# sc14cvm-evb.net
KiCad netlist of a schematic drawn in EAGLE
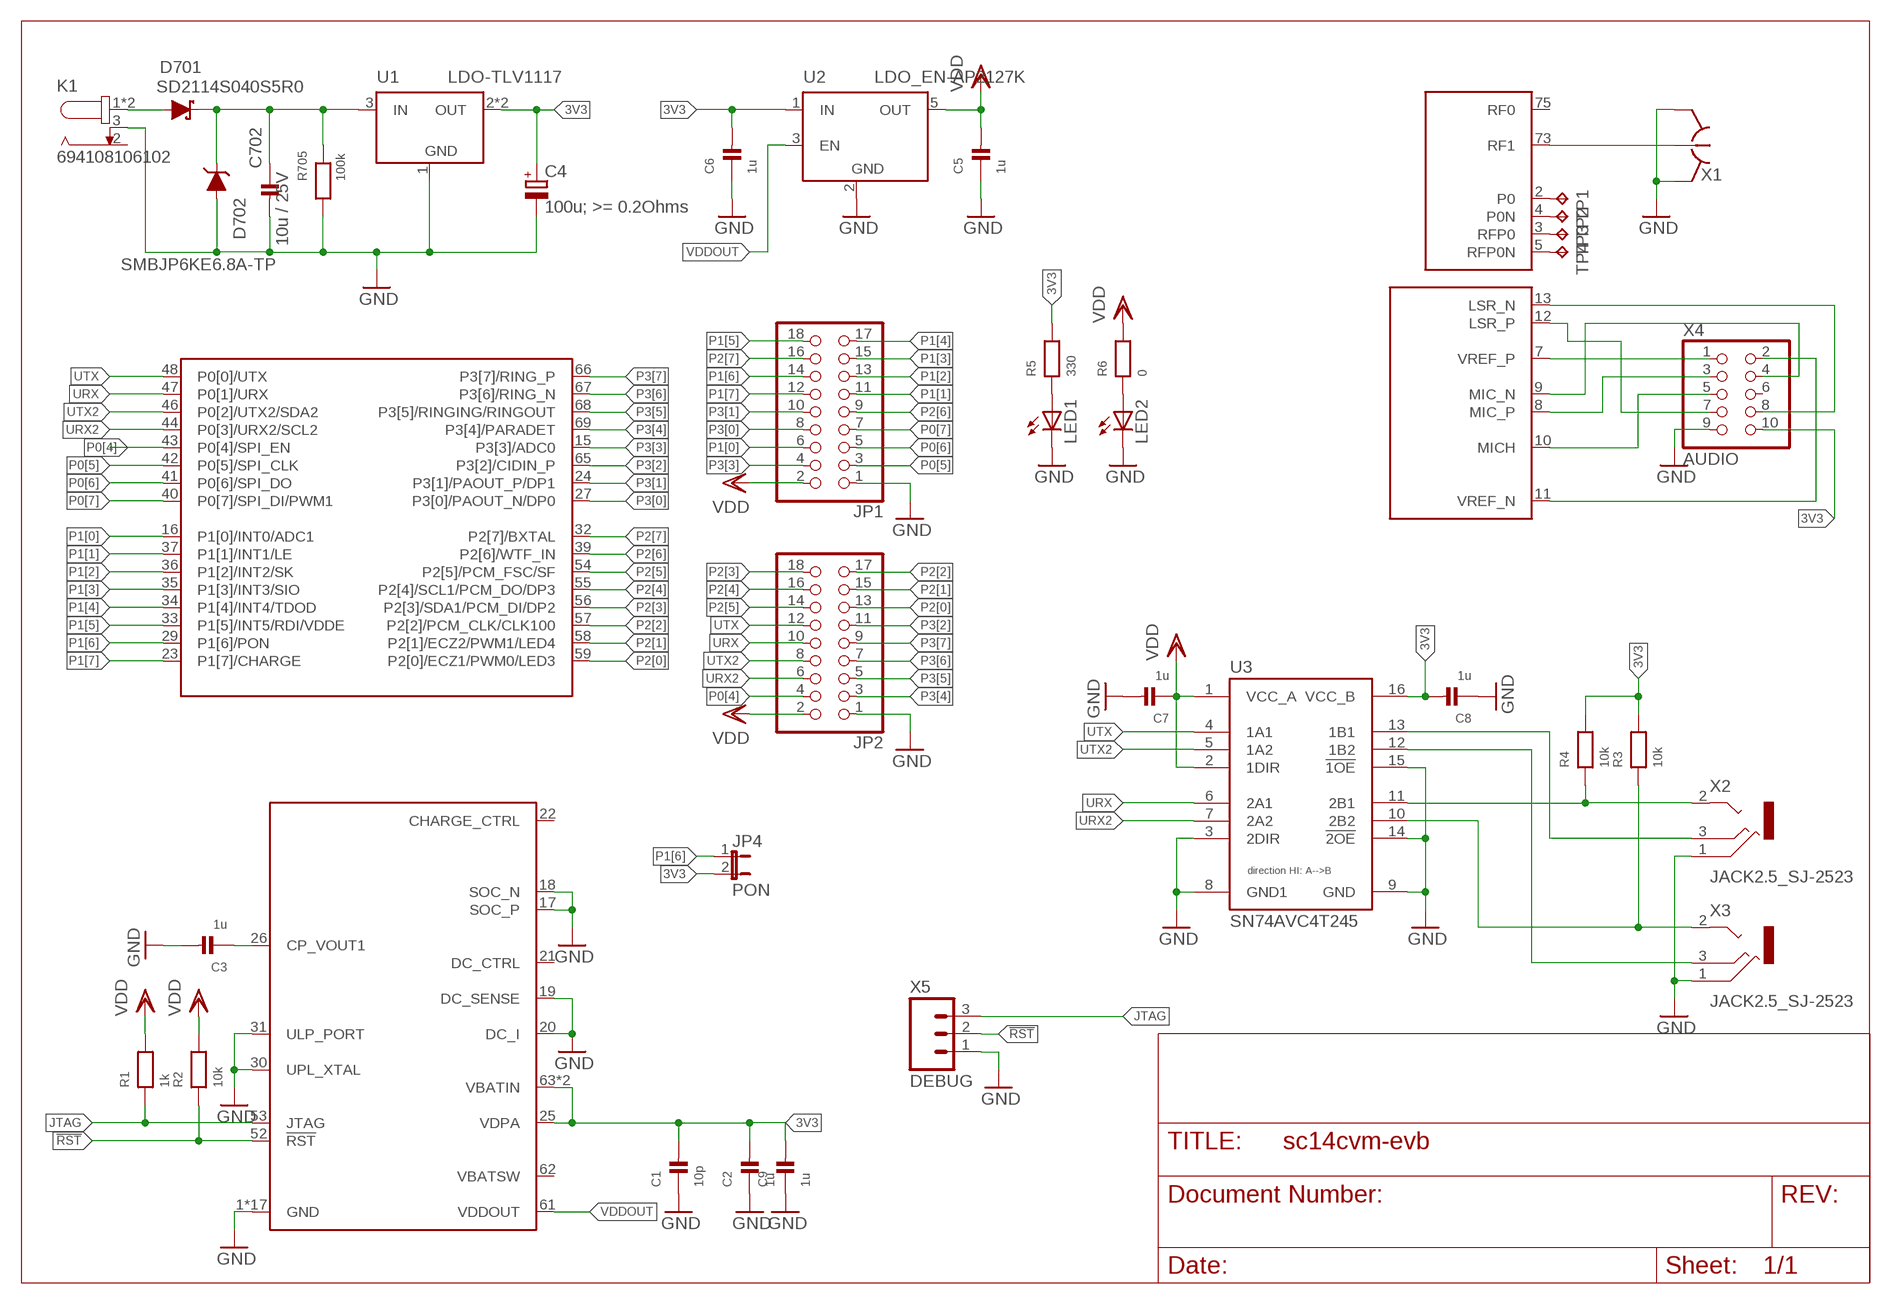
[diagram p0: schematic, sheet 1]

(export (version "E")
  (design (tool "Eeschema 10.0.6"))
  (components
    (comp (ref "C1")
      (value "10p")
      (footprint "eagle-import:_0402")
      (description "NO DESCRIPTION")
      (fields
        (field (name "MANUFACTURER") "UNKNOWN MANUFACTURER")
        (field (name "MANUFACTURERPARTNUMBER") "UNKNOWN MANUFACTURER PART NUMBER")
      )
      (libsource (lib "eagle-import") (part "CAP_CERAMIC_0402"))
    )
    (comp (ref "C2")
      (value "1u")
      (footprint "eagle-import:_0402")
      (description "NO DESCRIPTION")
      (fields
        (field (name "MANUFACTURER") "UNKNOWN MANUFACTURER")
        (field (name "MANUFACTURERPARTNUMBER") "UNKNOWN MANUFACTURER PART NUMBER")
      )
      (libsource (lib "eagle-import") (part "CAP_CERAMIC_0402"))
    )
    (comp (ref "C3")
      (value "1u")
      (footprint "eagle-import:_0603")
      (description "NO DESCRIPTION")
      (fields
        (field (name "MANUFACTURER") "UNKNOWN MANUFACTURER")
        (field (name "MANUFACTURERPARTNUMBER") "UNKNOWN MANUFACTURER PART NUMBER")
      )
      (libsource (lib "eagle-import") (part "CAP_CERAMIC_0603"))
    )
    (comp (ref "C4")
      (value "100u; >= 0.2Ohms")
      (footprint "eagle-import:SMC_B")
      (description "NO DESCRIPTION")
      (fields
        (field (name "MANUFACTURER") "UNKNOWN MANUFACTURER")
        (field (name "MANUFACTURERPARTNUMBER") "UNKNOWN MANUFACTURER PART NUMBER")
      )
      (libsource (lib "eagle-import") (part "CPOL-EUSMCB"))
    )
    (comp (ref "C5")
      (value "1u")
      (footprint "eagle-import:_0603")
      (description "NO DESCRIPTION")
      (fields
        (field (name "MANUFACTURER") "UNKNOWN MANUFACTURER")
        (field (name "MANUFACTURERPARTNUMBER") "UNKNOWN MANUFACTURER PART NUMBER")
      )
      (libsource (lib "eagle-import") (part "CAP_CERAMIC_0603"))
    )
    (comp (ref "C6")
      (value "1u")
      (footprint "eagle-import:_0603")
      (description "NO DESCRIPTION")
      (fields
        (field (name "MANUFACTURER") "UNKNOWN MANUFACTURER")
        (field (name "MANUFACTURERPARTNUMBER") "UNKNOWN MANUFACTURER PART NUMBER")
      )
      (libsource (lib "eagle-import") (part "CAP_CERAMIC_0603"))
    )
    (comp (ref "C7")
      (value "1u")
      (footprint "eagle-import:_0603")
      (description "NO DESCRIPTION")
      (fields
        (field (name "MANUFACTURER") "UNKNOWN MANUFACTURER")
        (field (name "MANUFACTURERPARTNUMBER") "UNKNOWN MANUFACTURER PART NUMBER")
      )
      (libsource (lib "eagle-import") (part "CAP_CERAMIC_0603"))
    )
    (comp (ref "C8")
      (value "1u")
      (footprint "eagle-import:_0603")
      (description "NO DESCRIPTION")
      (fields
        (field (name "MANUFACTURER") "UNKNOWN MANUFACTURER")
        (field (name "MANUFACTURERPARTNUMBER") "UNKNOWN MANUFACTURER PART NUMBER")
      )
      (libsource (lib "eagle-import") (part "CAP_CERAMIC_0603"))
    )
    (comp (ref "C9")
      (value "1u")
      (footprint "eagle-import:_0402")
      (description "NO DESCRIPTION")
      (fields
        (field (name "MANUFACTURER") "UNKNOWN MANUFACTURER")
        (field (name "MANUFACTURERPARTNUMBER") "UNKNOWN MANUFACTURER PART NUMBER")
      )
      (libsource (lib "eagle-import") (part "CAP_CERAMIC_0402"))
    )
    (comp (ref "C702")
      (value "10u / 25V")
      (footprint "eagle-import:C1812K")
      (description "CAP CER 10UF 25V X7R 1812")
      (fields
        (field (name "MANUFACTURER") "TDK Corporation")
        (field (name "MANUFACTURERPARTNUMBER") "C4532X7R1E106M250KA")
      )
      (libsource (lib "eagle-import") (part "CAP_CERAMIC-C1812"))
    )
    (comp (ref "D701")
      (value "SD2114S040S5R0")
      (footprint "eagle-import:SMBDIODE")
      (description "DIODE SCHOTTKY 40V 5A SMB")
      (fields (field (name "MANUFACTURER") "AVX Corporation"))
      (libsource (lib "eagle-import") (part "DIODE-SCHOTTKY-SMB"))
    )
    (comp (ref "D702")
      (value "SMBJP6KE6.8A-TP")
      (footprint "eagle-import:SMBDIODE")
      (description "TVS DIODE 5.8V 10.5V DO214AA")
      (fields (field (name "MANUFACTURER") "Micro Commercial Co"))
      (libsource (lib "eagle-import") (part "DIODE-TVS-SMB"))
    )
    (comp (ref "JP1")
      (value "PINHD-2X9")
      (footprint "eagle-import:2X09")
      (description "NO DESCRIPTION")
      (fields
        (field (name "MANUFACTURER") "UNKNOWN MANUFACTURER")
        (field (name "MANUFACTURERPARTNUMBER") "UNKNOWN MANUFACTURER PART NUMBER")
      )
      (libsource (lib "eagle-import") (part "PINHD-2X9"))
    )
    (comp (ref "JP2")
      (value "PINHD-2X9")
      (footprint "eagle-import:2X09")
      (description "NO DESCRIPTION")
      (fields
        (field (name "MANUFACTURER") "UNKNOWN MANUFACTURER")
        (field (name "MANUFACTURERPARTNUMBER") "UNKNOWN MANUFACTURER PART NUMBER")
      )
      (libsource (lib "eagle-import") (part "PINHD-2X9"))
    )
    (comp (ref "JP4")
      (value "PON")
      (footprint "eagle-import:JP1")
      (description "NO DESCRIPTION")
      (fields
        (field (name "MANUFACTURER") "UNKNOWN MANUFACTURER")
        (field (name "MANUFACTURERPARTNUMBER") "UNKNOWN MANUFACTURER PART NUMBER")
      )
      (libsource (lib "eagle-import") (part "JP1E"))
    )
    (comp (ref "K1")
      (value "694108106102")
      (footprint "eagle-import:694108106102")
      (description "NO DESCRIPTION")
      (fields
        (field (name "MANUFACTURER") "UNKNOWN MANUFACTURER")
        (field (name "MANUFACTURERPARTNUMBER") "UNKNOWN MANUFACTURER PART NUMBER")
      )
      (libsource (lib "eagle-import") (part "694108106102"))
    )
    (comp (ref "LED1")
      (value "LEDCHIPLED_0603")
      (footprint "eagle-import:CHIPLED_0603")
      (description "NO DESCRIPTION")
      (fields
        (field (name "MANUFACTURER") "UNKNOWN MANUFACTURER")
        (field (name "MANUFACTURERPARTNUMBER") "UNKNOWN MANUFACTURER PART NUMBER")
      )
      (libsource (lib "eagle-import") (part "LEDCHIPLED_0603"))
    )
    (comp (ref "LED2")
      (value "LEDCHIPLED_0603")
      (footprint "eagle-import:CHIPLED_0603")
      (description "NO DESCRIPTION")
      (fields
        (field (name "MANUFACTURER") "UNKNOWN MANUFACTURER")
        (field (name "MANUFACTURERPARTNUMBER") "UNKNOWN MANUFACTURER PART NUMBER")
      )
      (libsource (lib "eagle-import") (part "LEDCHIPLED_0603"))
    )
    (comp (ref "MOD1")
      (value "SC14CVMDECT")
      (footprint "eagle-import:MOD88")
      (description "NO DESCRIPTION")
      (fields
        (field (name "MANUFACTURER") "UNKNOWN MANUFACTURER")
        (field (name "MANUFACTURERPARTNUMBER") "UNKNOWN MANUFACTURER PART NUMBER")
        (field (name "CLASS") "UNKNOWN CLASS")
        (field (name "LINK") "UNKNOWN LINK")
        (field (name "POPULATED") "TRUE")
        (field (name "ROHSCERTIFICATE") "UNKNOWN ROHS CERTIFICATE")
        (field (name "SOURCE") "UNKNOWN SOURCE")
        (field (name "SOURCEPARTNUMBER") "UNKNOWN SOURCE PART NUMBER")
      )
      (libsource (lib "eagle-import") (part "SC14CVMDECT"))
    )
    (comp (ref "R1")
      (value "1k")
      (footprint "eagle-import:_0603@2")
      (description "NO DESCRIPTION")
      (fields
        (field (name "MANUFACTURER") "UNKNOWN MANUFACTURER")
        (field (name "MANUFACTURERPARTNUMBER") "UNKNOWN MANUFACTURER PART NUMBER")
      )
      (libsource (lib "eagle-import") (part "RESISTOR_0603"))
    )
    (comp (ref "R2")
      (value "10k")
      (footprint "eagle-import:_0603@2")
      (description "NO DESCRIPTION")
      (fields
        (field (name "MANUFACTURER") "UNKNOWN MANUFACTURER")
        (field (name "MANUFACTURERPARTNUMBER") "UNKNOWN MANUFACTURER PART NUMBER")
      )
      (libsource (lib "eagle-import") (part "RESISTOR_0603"))
    )
    (comp (ref "R3")
      (value "10k")
      (footprint "eagle-import:_0603@2")
      (description "NO DESCRIPTION")
      (fields
        (field (name "MANUFACTURER") "UNKNOWN MANUFACTURER")
        (field (name "MANUFACTURERPARTNUMBER") "UNKNOWN MANUFACTURER PART NUMBER")
      )
      (libsource (lib "eagle-import") (part "RESISTOR_0603"))
    )
    (comp (ref "R4")
      (value "10k")
      (footprint "eagle-import:_0603@2")
      (description "NO DESCRIPTION")
      (fields
        (field (name "MANUFACTURER") "UNKNOWN MANUFACTURER")
        (field (name "MANUFACTURERPARTNUMBER") "UNKNOWN MANUFACTURER PART NUMBER")
      )
      (libsource (lib "eagle-import") (part "RESISTOR_0603"))
    )
    (comp (ref "R5")
      (value "330")
      (footprint "eagle-import:_0603@2")
      (description "NO DESCRIPTION")
      (fields
        (field (name "MANUFACTURER") "UNKNOWN MANUFACTURER")
        (field (name "MANUFACTURERPARTNUMBER") "UNKNOWN MANUFACTURER PART NUMBER")
      )
      (libsource (lib "eagle-import") (part "RESISTOR_0603"))
    )
    (comp (ref "R6")
      (value "0")
      (footprint "eagle-import:_0603@2")
      (description "NO DESCRIPTION")
      (fields
        (field (name "MANUFACTURER") "UNKNOWN MANUFACTURER")
        (field (name "MANUFACTURERPARTNUMBER") "UNKNOWN MANUFACTURER PART NUMBER")
      )
      (libsource (lib "eagle-import") (part "RESISTOR_0603"))
    )
    (comp (ref "R705")
      (value "100k")
      (footprint "eagle-import:_0603@2")
      (description "RES SMD 100K OHM 1%% 1/10W 0603")
      (fields
        (field (name "MANUFACTURER") "Vishay Dale")
        (field (name "MANUFACTURERPARTNUMBER") "CRCW0603100KFKEA")
      )
      (libsource (lib "eagle-import") (part "RESISTOR_0603"))
    )
    (comp (ref "TP1")
      (value "TPTP11R")
      (footprint "eagle-import:TP11R")
      (description "NO DESCRIPTION")
      (fields
        (field (name "MANUFACTURER") "UNKNOWN MANUFACTURER")
        (field (name "MANUFACTURERPARTNUMBER") "UNKNOWN MANUFACTURER PART NUMBER")
      )
      (libsource (lib "eagle-import") (part "TPTP11R"))
    )
    (comp (ref "TP2")
      (value "TPTP11R")
      (footprint "eagle-import:TP11R")
      (description "NO DESCRIPTION")
      (fields
        (field (name "MANUFACTURER") "UNKNOWN MANUFACTURER")
        (field (name "MANUFACTURERPARTNUMBER") "UNKNOWN MANUFACTURER PART NUMBER")
      )
      (libsource (lib "eagle-import") (part "TPTP11R"))
    )
    (comp (ref "TP3")
      (value "TPTP11R")
      (footprint "eagle-import:TP11R")
      (description "NO DESCRIPTION")
      (fields
        (field (name "MANUFACTURER") "UNKNOWN MANUFACTURER")
        (field (name "MANUFACTURERPARTNUMBER") "UNKNOWN MANUFACTURER PART NUMBER")
      )
      (libsource (lib "eagle-import") (part "TPTP11R"))
    )
    (comp (ref "TP4")
      (value "TPTP11R")
      (footprint "eagle-import:TP11R")
      (description "NO DESCRIPTION")
      (fields
        (field (name "MANUFACTURER") "UNKNOWN MANUFACTURER")
        (field (name "MANUFACTURERPARTNUMBER") "UNKNOWN MANUFACTURER PART NUMBER")
      )
      (libsource (lib "eagle-import") (part "TPTP11R"))
    )
    (comp (ref "U1")
      (value "LDO-TLV1117")
      (footprint "eagle-import:SOT223")
      (description "NO DESCRIPTION")
      (fields
        (field (name "MANUFACTURER") "UNKNOWN MANUFACTURER")
        (field (name "MANUFACTURERPARTNUMBER") "UNKNOWN MANUFACTURER PART NUMBER")
      )
      (libsource (lib "eagle-import") (part "LDO-TLV1117"))
    )
    (comp (ref "U2")
      (value "LDO_EN-AP2127K")
      (footprint "eagle-import:SOT23L")
      (description "NO DESCRIPTION")
      (fields
        (field (name "MANUFACTURER") "UNKNOWN MANUFACTURER")
        (field (name "MANUFACTURERPARTNUMBER") "AP2127K-1.8TRG1")
      )
      (libsource (lib "eagle-import") (part "LDO_EN-AP2127K"))
    )
    (comp (ref "U3")
      (value "SN74AVC4T245")
      (footprint "eagle-import:TSSOP16")
      (description "NO DESCRIPTION")
      (fields
        (field (name "MANUFACTURER") "UNKNOWN MANUFACTURER")
        (field (name "MANUFACTURERPARTNUMBER") "UNKNOWN MANUFACTURER PART NUMBER")
      )
      (libsource (lib "eagle-import") (part "SN74AVC4T245"))
    )
    (comp (ref "X1")
      (value "HRS_UFL")
      (footprint "eagle-import:HRS_UFL")
      (description "NO DESCRIPTION")
      (fields
        (field (name "MANUFACTURER") "UNKNOWN MANUFACTURER")
        (field (name "MANUFACTURERPARTNUMBER") "UNKNOWN MANUFACTURER PART NUMBER")
      )
      (libsource (lib "eagle-import") (part "HRS_UFL"))
    )
    (comp (ref "X2")
      (value "JACK2.5_SJ-2523")
      (footprint "eagle-import:JACK2.5_SJ-2523")
      (description "NO DESCRIPTION")
      (fields
        (field (name "MANUFACTURER") "UNKNOWN MANUFACTURER")
        (field (name "MANUFACTURERPARTNUMBER") "UNKNOWN MANUFACTURER PART NUMBER")
      )
      (libsource (lib "eagle-import") (part "JACK2.5_SJ-2523"))
    )
    (comp (ref "X3")
      (value "JACK2.5_SJ-2523")
      (footprint "eagle-import:JACK2.5_SJ-2523")
      (description "NO DESCRIPTION")
      (fields
        (field (name "MANUFACTURER") "UNKNOWN MANUFACTURER")
        (field (name "MANUFACTURERPARTNUMBER") "UNKNOWN MANUFACTURER PART NUMBER")
      )
      (libsource (lib "eagle-import") (part "JACK2.5_SJ-2523"))
    )
    (comp (ref "X4")
      (value "AUDIO")
      (footprint "eagle-import:2X05")
      (description "NO DESCRIPTION")
      (fields
        (field (name "MANUFACTURER") "UNKNOWN MANUFACTURER")
        (field (name "MANUFACTURERPARTNUMBER") "UNKNOWN MANUFACTURER PART NUMBER")
      )
      (libsource (lib "eagle-import") (part "PINHD-2X5"))
    )
    (comp (ref "X5")
      (value "DEBUG")
      (footprint "eagle-import:1X03_LOCK_LONGPADS")
      (description "NO DESCRIPTION")
      (fields
        (field (name "MANUFACTURER") "UNKNOWN MANUFACTURER")
        (field (name "MANUFACTURERPARTNUMBER") "UNKNOWN MANUFACTURER PART NUMBER")
      )
      (libsource (lib "eagle-import") (part "PINHD-1X3LOCK_LONGPADS"))
    )
  )
  (nets
    (net (code "1") (name "/~{RST}") (class "Default")
      (node (ref "MOD1") (pin "52") (pinfunction "~{RST}_52") (pintype "bidirectional"))
      (node (ref "R2") (pin "1") (pinfunction "1_1") (pintype "passive"))
      (node (ref "X5") (pin "2") (pinfunction "2_2") (pintype "passive"))
    )
    (net (code "2") (name "3V3") (class "Default")
      (node (ref "C1") (pin "2") (pinfunction "2_2") (pintype "passive"))
      (node (ref "C2") (pin "2") (pinfunction "2_2") (pintype "passive"))
      (node (ref "C4") (pin "+") (pinfunction "+_+") (pintype "passive"))
      (node (ref "C6") (pin "2") (pinfunction "2_2") (pintype "passive"))
      (node (ref "C8") (pin "2") (pinfunction "2_2") (pintype "passive"))
      (node (ref "C9") (pin "2") (pinfunction "2_2") (pintype "passive"))
      (node (ref "JP4") (pin "2") (pinfunction "2_2") (pintype "passive"))
      (node (ref "MOD1") (pin "25") (pinfunction "VDPA_25") (pintype "bidirectional"))
      (node (ref "MOD1") (pin "63") (pinfunction "VBATIN_63") (pintype "bidirectional"))
      (node (ref "MOD1") (pin "64") (pinfunction "VBATIN_64") (pintype "bidirectional"))
      (node (ref "R3") (pin "2") (pinfunction "2_2") (pintype "passive"))
      (node (ref "R4") (pin "2") (pinfunction "2_2") (pintype "passive"))
      (node (ref "R5") (pin "2") (pinfunction "2_2") (pintype "passive"))
      (node (ref "U1") (pin "2") (pinfunction "OUT_2") (pintype "passive"))
      (node (ref "U1") (pin "4") (pinfunction "OUT_4") (pintype "passive"))
      (node (ref "U2") (pin "1") (pinfunction "IN_1") (pintype "input"))
      (node (ref "U3") (pin "16") (pinfunction "VCC_B_16") (pintype "power_in"))
      (node (ref "X4") (pin "10") (pinfunction "10_10") (pintype "passive"))
    )
    (net (code "3") (name "GND") (class "Default")
      (node (ref "C1") (pin "1") (pinfunction "1_1") (pintype "passive"))
      (node (ref "C2") (pin "1") (pinfunction "1_1") (pintype "passive"))
      (node (ref "C3") (pin "2") (pinfunction "2_2") (pintype "passive"))
      (node (ref "C4") (pin "-") (pinfunction "-_-") (pintype "passive"))
      (node (ref "C5") (pin "1") (pinfunction "1_1") (pintype "passive"))
      (node (ref "C6") (pin "1") (pinfunction "1_1") (pintype "passive"))
      (node (ref "C7") (pin "2") (pinfunction "2_2") (pintype "passive"))
      (node (ref "C702") (pin "2") (pinfunction "2_2") (pintype "passive"))
      (node (ref "C8") (pin "1") (pinfunction "1_1") (pintype "passive"))
      (node (ref "C9") (pin "1") (pinfunction "1_1") (pintype "passive"))
      (node (ref "D702") (pin "A") (pinfunction "A_A") (pintype "passive"))
      (node (ref "JP1") (pin "1") (pinfunction "1_1") (pintype "passive"))
      (node (ref "JP2") (pin "1") (pinfunction "1_1") (pintype "passive"))
      (node (ref "K1") (pin "3") (pinfunction "3_3") (pintype "passive"))
      (node (ref "LED1") (pin "C") (pinfunction "C_C") (pintype "passive"))
      (node (ref "LED2") (pin "C") (pinfunction "C_C") (pintype "passive"))
      (node (ref "MOD1") (pin "1") (pinfunction "GND_1") (pintype "bidirectional"))
      (node (ref "MOD1") (pin "14") (pinfunction "GND_14") (pintype "bidirectional"))
      (node (ref "MOD1") (pin "17") (pinfunction "SOC_P_17") (pintype "bidirectional"))
      (node (ref "MOD1") (pin "18") (pinfunction "SOC_N_18") (pintype "bidirectional"))
      (node (ref "MOD1") (pin "19") (pinfunction "DC_SENSE_19") (pintype "bidirectional"))
      (node (ref "MOD1") (pin "20") (pinfunction "DC_I_20") (pintype "bidirectional"))
      (node (ref "MOD1") (pin "28") (pinfunction "GND_28") (pintype "bidirectional"))
      (node (ref "MOD1") (pin "30") (pinfunction "UPL_XTAL_30") (pintype "bidirectional"))
      (node (ref "MOD1") (pin "31") (pinfunction "ULP_PORT_31") (pintype "bidirectional"))
      (node (ref "MOD1") (pin "38") (pinfunction "GND_38") (pintype "bidirectional"))
      (node (ref "MOD1") (pin "45") (pinfunction "GND_45") (pintype "bidirectional"))
      (node (ref "MOD1") (pin "49") (pinfunction "GND_49") (pintype "bidirectional"))
      (node (ref "MOD1") (pin "50") (pinfunction "GND_50") (pintype "bidirectional"))
      (node (ref "MOD1") (pin "51") (pinfunction "GND_51") (pintype "bidirectional"))
      (node (ref "MOD1") (pin "6") (pinfunction "GND_6") (pintype "bidirectional"))
      (node (ref "MOD1") (pin "60") (pinfunction "GND_60") (pintype "bidirectional"))
      (node (ref "MOD1") (pin "70") (pinfunction "GND_70") (pintype "bidirectional"))
      (node (ref "MOD1") (pin "71") (pinfunction "GND_71") (pintype "bidirectional"))
      (node (ref "MOD1") (pin "72") (pinfunction "GND_72") (pintype "bidirectional"))
      (node (ref "MOD1") (pin "74") (pinfunction "GND_74") (pintype "bidirectional"))
      (node (ref "MOD1") (pin "76") (pinfunction "GND_76") (pintype "bidirectional"))
      (node (ref "MOD1") (pin "77") (pinfunction "GND_77") (pintype "bidirectional"))
      (node (ref "MOD1") (pin "78") (pinfunction "GND_78") (pintype "bidirectional"))
      (node (ref "R705") (pin "1") (pinfunction "1_1") (pintype "passive"))
      (node (ref "U1") (pin "1") (pinfunction "GND_1") (pintype "power_in"))
      (node (ref "U2") (pin "2") (pinfunction "GND_2") (pintype "power_in"))
      (node (ref "U3") (pin "14") (pinfunction "~{2OE}_14") (pintype "input"))
      (node (ref "U3") (pin "15") (pinfunction "~{1OE}_15") (pintype "input"))
      (node (ref "U3") (pin "3") (pinfunction "2DIR_3") (pintype "input"))
      (node (ref "U3") (pin "8") (pinfunction "GND1_8") (pintype "passive"))
      (node (ref "U3") (pin "9") (pinfunction "GND_9") (pintype "passive"))
      (node (ref "X1") (pin "GND@1") (pinfunction "GND_GND@1") (pintype "power_in"))
      (node (ref "X1") (pin "GND@2") (pinfunction "GND_GND@2") (pintype "power_in"))
      (node (ref "X2") (pin "1") (pinfunction "RING_1") (pintype "passive"))
      (node (ref "X3") (pin "1") (pinfunction "RING_1") (pintype "passive"))
      (node (ref "X4") (pin "9") (pinfunction "9_9") (pintype "passive"))
      (node (ref "X5") (pin "1") (pinfunction "1_1") (pintype "passive"))
    )
    (net (code "4") (name "JTAG") (class "Default")
      (node (ref "MOD1") (pin "53") (pinfunction "JTAG_53") (pintype "bidirectional"))
      (node (ref "R1") (pin "1") (pinfunction "1_1") (pintype "passive"))
      (node (ref "X5") (pin "3") (pinfunction "3_3") (pintype "passive"))
    )
    (net (code "5") (name "Net-(D701-PadA)") (class "Default")
      (node (ref "D701") (pin "A") (pinfunction "A_A") (pintype "passive"))
      (node (ref "K1") (pin "1") (pinfunction "1_1") (pintype "passive"))
      (node (ref "K1") (pin "1-1") (pinfunction "1_1-1") (pintype "passive"))
    )
    (net (code "6") (name "Net-(LED1-PadA)") (class "Default")
      (node (ref "LED1") (pin "A") (pinfunction "A_A") (pintype "passive"))
      (node (ref "R5") (pin "1") (pinfunction "1_1") (pintype "passive"))
    )
    (net (code "7") (name "Net-(LED2-PadA)") (class "Default")
      (node (ref "LED2") (pin "A") (pinfunction "A_A") (pintype "passive"))
      (node (ref "R6") (pin "1") (pinfunction "1_1") (pintype "passive"))
    )
    (net (code "8") (name "Net-(MOD1A-LSR_N)") (class "Default")
      (node (ref "MOD1") (pin "13") (pinfunction "LSR_N_13") (pintype "bidirectional"))
      (node (ref "X4") (pin "8") (pinfunction "8_8") (pintype "passive"))
    )
    (net (code "9") (name "Net-(MOD1A-LSR_P)") (class "Default")
      (node (ref "MOD1") (pin "12") (pinfunction "LSR_P_12") (pintype "bidirectional"))
      (node (ref "X4") (pin "7") (pinfunction "7_7") (pintype "passive"))
    )
    (net (code "10") (name "Net-(MOD1A-MICH)") (class "Default")
      (node (ref "MOD1") (pin "10") (pinfunction "MICH_10") (pintype "bidirectional"))
      (node (ref "X4") (pin "5") (pinfunction "5_5") (pintype "passive"))
    )
    (net (code "11") (name "Net-(MOD1A-MIC_N)") (class "Default")
      (node (ref "MOD1") (pin "9") (pinfunction "MIC_N_9") (pintype "bidirectional"))
      (node (ref "X4") (pin "4") (pinfunction "4_4") (pintype "passive"))
    )
    (net (code "12") (name "Net-(MOD1A-MIC_P)") (class "Default")
      (node (ref "MOD1") (pin "8") (pinfunction "MIC_P_8") (pintype "bidirectional"))
      (node (ref "X4") (pin "3") (pinfunction "3_3") (pintype "passive"))
    )
    (net (code "13") (name "Net-(MOD1A-VREF_N)") (class "Default")
      (node (ref "MOD1") (pin "11") (pinfunction "VREF_N_11") (pintype "bidirectional"))
      (node (ref "X4") (pin "2") (pinfunction "2_2") (pintype "passive"))
    )
    (net (code "14") (name "Net-(MOD1A-VREF_P)") (class "Default")
      (node (ref "MOD1") (pin "7") (pinfunction "VREF_P_7") (pintype "bidirectional"))
      (node (ref "X4") (pin "1") (pinfunction "1_1") (pintype "passive"))
    )
    (net (code "15") (name "Net-(MOD1C-P0)") (class "Default")
      (node (ref "MOD1") (pin "2") (pinfunction "P0_2") (pintype "output"))
      (node (ref "TP1") (pin "TP") (pinfunction "TP_TP") (pintype "input"))
    )
    (net (code "16") (name "Net-(MOD1C-P0N)") (class "Default")
      (node (ref "MOD1") (pin "4") (pinfunction "P0N_4") (pintype "output"))
      (node (ref "TP2") (pin "TP") (pinfunction "TP_TP") (pintype "input"))
    )
    (net (code "17") (name "Net-(MOD1C-RF1)") (class "Default")
      (node (ref "MOD1") (pin "73") (pinfunction "RF1_73") (pintype "passive"))
      (node (ref "X1") (pin "SIG") (pinfunction "1_SIG") (pintype "passive"))
    )
    (net (code "18") (name "Net-(MOD1C-RFP0)") (class "Default")
      (node (ref "MOD1") (pin "3") (pinfunction "RFP0_3") (pintype "output"))
      (node (ref "TP3") (pin "TP") (pinfunction "TP_TP") (pintype "input"))
    )
    (net (code "19") (name "Net-(MOD1C-RFP0N)") (class "Default")
      (node (ref "MOD1") (pin "5") (pinfunction "RFP0N_5") (pintype "output"))
      (node (ref "TP4") (pin "TP") (pinfunction "TP_TP") (pintype "input"))
    )
    (net (code "20") (name "Net-(MOD1D-CP_VOUT1)") (class "Default")
      (node (ref "C3") (pin "1") (pinfunction "1_1") (pintype "passive"))
      (node (ref "MOD1") (pin "26") (pinfunction "CP_VOUT1_26") (pintype "bidirectional"))
    )
    (net (code "21") (name "Net-(U1-IN)") (class "Default")
      (node (ref "C702") (pin "1") (pinfunction "1_1") (pintype "passive"))
      (node (ref "D701") (pin "C") (pinfunction "C_C") (pintype "passive"))
      (node (ref "D702") (pin "C") (pinfunction "C_C") (pintype "passive"))
      (node (ref "R705") (pin "2") (pinfunction "2_2") (pintype "passive"))
      (node (ref "U1") (pin "3") (pinfunction "IN_3") (pintype "input"))
    )
    (net (code "22") (name "Net-(U3-1B1)") (class "Default")
      (node (ref "U3") (pin "13") (pinfunction "1B1_13") (pintype "bidirectional"))
      (node (ref "X2") (pin "3") (pinfunction "MIDDLE_3") (pintype "passive"))
    )
    (net (code "23") (name "Net-(U3-1B2)") (class "Default")
      (node (ref "U3") (pin "12") (pinfunction "1B2_12") (pintype "bidirectional"))
      (node (ref "X3") (pin "3") (pinfunction "MIDDLE_3") (pintype "passive"))
    )
    (net (code "24") (name "Net-(U3-2B1)") (class "Default")
      (node (ref "R4") (pin "1") (pinfunction "1_1") (pintype "passive"))
      (node (ref "U3") (pin "11") (pinfunction "2B1_11") (pintype "bidirectional"))
      (node (ref "X2") (pin "2") (pinfunction "TIP_2") (pintype "passive"))
    )
    (net (code "25") (name "Net-(U3-2B2)") (class "Default")
      (node (ref "R3") (pin "1") (pinfunction "1_1") (pintype "passive"))
      (node (ref "U3") (pin "10") (pinfunction "2B2_10") (pintype "bidirectional"))
      (node (ref "X3") (pin "2") (pinfunction "TIP_2") (pintype "passive"))
    )
    (net (code "26") (name "P0[4]") (class "Default")
      (node (ref "JP2") (pin "4") (pinfunction "4_4") (pintype "passive"))
      (node (ref "MOD1") (pin "43") (pinfunction "P0[4]/SPI_EN_43") (pintype "bidirectional"))
    )
    (net (code "27") (name "P0[5]") (class "Default")
      (node (ref "JP1") (pin "3") (pinfunction "3_3") (pintype "passive"))
      (node (ref "MOD1") (pin "42") (pinfunction "P0[5]/SPI_CLK_42") (pintype "bidirectional"))
    )
    (net (code "28") (name "P0[6]") (class "Default")
      (node (ref "JP1") (pin "5") (pinfunction "5_5") (pintype "passive"))
      (node (ref "MOD1") (pin "41") (pinfunction "P0[6]/SPI_DO_41") (pintype "bidirectional"))
    )
    (net (code "29") (name "P0[7]") (class "Default")
      (node (ref "JP1") (pin "7") (pinfunction "7_7") (pintype "passive"))
      (node (ref "MOD1") (pin "40") (pinfunction "P0[7]/SPI_DI/PWM1_40") (pintype "bidirectional"))
    )
    (net (code "30") (name "P1[0]") (class "Default")
      (node (ref "JP1") (pin "6") (pinfunction "6_6") (pintype "passive"))
      (node (ref "MOD1") (pin "16") (pinfunction "P1[0]/INT0/ADC1_16") (pintype "bidirectional"))
    )
    (net (code "31") (name "P1[1]") (class "Default")
      (node (ref "JP1") (pin "11") (pinfunction "11_11") (pintype "passive"))
      (node (ref "MOD1") (pin "37") (pinfunction "P1[1]/INT1/LE_37") (pintype "bidirectional"))
    )
    (net (code "32") (name "P1[2]") (class "Default")
      (node (ref "JP1") (pin "13") (pinfunction "13_13") (pintype "passive"))
      (node (ref "MOD1") (pin "36") (pinfunction "P1[2]/INT2/SK_36") (pintype "bidirectional"))
    )
    (net (code "33") (name "P1[3]") (class "Default")
      (node (ref "JP1") (pin "15") (pinfunction "15_15") (pintype "passive"))
      (node (ref "MOD1") (pin "35") (pinfunction "P1[3]/INT3/SIO_35") (pintype "bidirectional"))
    )
    (net (code "34") (name "P1[4]") (class "Default")
      (node (ref "JP1") (pin "17") (pinfunction "17_17") (pintype "passive"))
      (node (ref "MOD1") (pin "34") (pinfunction "P1[4]/INT4/TDOD_34") (pintype "bidirectional"))
    )
    (net (code "35") (name "P1[5]") (class "Default")
      (node (ref "JP1") (pin "18") (pinfunction "18_18") (pintype "passive"))
      (node (ref "MOD1") (pin "33") (pinfunction "P1[5]/INT5/RDI/VDDE_33") (pintype "bidirectional"))
    )
    (net (code "36") (name "P1[6]") (class "Default")
      (node (ref "JP1") (pin "14") (pinfunction "14_14") (pintype "passive"))
      (node (ref "JP4") (pin "1") (pinfunction "1_1") (pintype "passive"))
      (node (ref "MOD1") (pin "29") (pinfunction "P1[6]/PON_29") (pintype "bidirectional"))
    )
    (net (code "37") (name "P1[7]") (class "Default")
      (node (ref "JP1") (pin "12") (pinfunction "12_12") (pintype "passive"))
      (node (ref "MOD1") (pin "23") (pinfunction "P1[7]/CHARGE_23") (pintype "bidirectional"))
    )
    (net (code "38") (name "P2[0]") (class "Default")
      (node (ref "JP2") (pin "13") (pinfunction "13_13") (pintype "passive"))
      (node (ref "MOD1") (pin "59") (pinfunction "P2[0]/ECZ1/PWM0/LED3_59") (pintype "bidirectional"))
    )
    (net (code "39") (name "P2[1]") (class "Default")
      (node (ref "JP2") (pin "15") (pinfunction "15_15") (pintype "passive"))
      (node (ref "MOD1") (pin "58") (pinfunction "P2[1]/ECZ2/PWM1/LED4_58") (pintype "bidirectional"))
    )
    (net (code "40") (name "P2[2]") (class "Default")
      (node (ref "JP2") (pin "17") (pinfunction "17_17") (pintype "passive"))
      (node (ref "MOD1") (pin "57") (pinfunction "P2[2]/PCM_CLK/CLK100_57") (pintype "bidirectional"))
    )
    (net (code "41") (name "P2[3]") (class "Default")
      (node (ref "JP2") (pin "18") (pinfunction "18_18") (pintype "passive"))
      (node (ref "MOD1") (pin "56") (pinfunction "P2[3]/SDA1/PCM_DI/DP2_56") (pintype "bidirectional"))
    )
    (net (code "42") (name "P2[4]") (class "Default")
      (node (ref "JP2") (pin "16") (pinfunction "16_16") (pintype "passive"))
      (node (ref "MOD1") (pin "55") (pinfunction "P2[4]/SCL1/PCM_DO/DP3_55") (pintype "bidirectional"))
    )
    (net (code "43") (name "P2[5]") (class "Default")
      (node (ref "JP2") (pin "14") (pinfunction "14_14") (pintype "passive"))
      (node (ref "MOD1") (pin "54") (pinfunction "P2[5]/PCM_FSC/SF_54") (pintype "bidirectional"))
    )
    (net (code "44") (name "P2[6]") (class "Default")
      (node (ref "JP1") (pin "9") (pinfunction "9_9") (pintype "passive"))
      (node (ref "MOD1") (pin "39") (pinfunction "P2[6]/WTF_IN_39") (pintype "bidirectional"))
    )
    (net (code "45") (name "P2[7]") (class "Default")
      (node (ref "JP1") (pin "16") (pinfunction "16_16") (pintype "passive"))
      (node (ref "MOD1") (pin "32") (pinfunction "P2[7]/BXTAL_32") (pintype "bidirectional"))
    )
    (net (code "46") (name "P3[0]") (class "Default")
      (node (ref "JP1") (pin "8") (pinfunction "8_8") (pintype "passive"))
      (node (ref "MOD1") (pin "27") (pinfunction "P3[0]/PAOUT_N/DP0_27") (pintype "bidirectional"))
    )
    (net (code "47") (name "P3[1]") (class "Default")
      (node (ref "JP1") (pin "10") (pinfunction "10_10") (pintype "passive"))
      (node (ref "MOD1") (pin "24") (pinfunction "P3[1]/PAOUT_P/DP1_24") (pintype "bidirectional"))
    )
    (net (code "48") (name "P3[2]") (class "Default")
      (node (ref "JP2") (pin "11") (pinfunction "11_11") (pintype "passive"))
      (node (ref "MOD1") (pin "65") (pinfunction "P3[2]/CIDIN_P_65") (pintype "bidirectional"))
    )
    (net (code "49") (name "P3[3]") (class "Default")
      (node (ref "JP1") (pin "4") (pinfunction "4_4") (pintype "passive"))
      (node (ref "MOD1") (pin "15") (pinfunction "P3[3]/ADC0_15") (pintype "bidirectional"))
    )
    (net (code "50") (name "P3[4]") (class "Default")
      (node (ref "JP2") (pin "3") (pinfunction "3_3") (pintype "passive"))
      (node (ref "MOD1") (pin "69") (pinfunction "P3[4]/PARADET_69") (pintype "bidirectional"))
    )
    (net (code "51") (name "P3[5]") (class "Default")
      (node (ref "JP2") (pin "5") (pinfunction "5_5") (pintype "passive"))
      (node (ref "MOD1") (pin "68") (pinfunction "P3[5]/RINGING/RINGOUT_68") (pintype "bidirectional"))
    )
    (net (code "52") (name "P3[6]") (class "Default")
      (node (ref "JP2") (pin "7") (pinfunction "7_7") (pintype "passive"))
      (node (ref "MOD1") (pin "67") (pinfunction "P3[6]/RING_N_67") (pintype "bidirectional"))
    )
    (net (code "53") (name "P3[7]") (class "Default")
      (node (ref "JP2") (pin "9") (pinfunction "9_9") (pintype "passive"))
      (node (ref "MOD1") (pin "66") (pinfunction "P3[7]/RING_P_66") (pintype "bidirectional"))
    )
    (net (code "54") (name "URX") (class "Default")
      (node (ref "JP2") (pin "10") (pinfunction "10_10") (pintype "passive"))
      (node (ref "MOD1") (pin "47") (pinfunction "P0[1]/URX_47") (pintype "bidirectional"))
      (node (ref "U3") (pin "6") (pinfunction "2A1_6") (pintype "bidirectional"))
    )
    (net (code "55") (name "URX2") (class "Default")
      (node (ref "JP2") (pin "6") (pinfunction "6_6") (pintype "passive"))
      (node (ref "MOD1") (pin "44") (pinfunction "P0[3]/URX2/SCL2_44") (pintype "bidirectional"))
      (node (ref "U3") (pin "7") (pinfunction "2A2_7") (pintype "bidirectional"))
    )
    (net (code "56") (name "UTX") (class "Default")
      (node (ref "JP2") (pin "12") (pinfunction "12_12") (pintype "passive"))
      (node (ref "MOD1") (pin "48") (pinfunction "P0[0]/UTX_48") (pintype "bidirectional"))
      (node (ref "U3") (pin "4") (pinfunction "1A1_4") (pintype "bidirectional"))
    )
    (net (code "57") (name "UTX2") (class "Default")
      (node (ref "JP2") (pin "8") (pinfunction "8_8") (pintype "passive"))
      (node (ref "MOD1") (pin "46") (pinfunction "P0[2]/UTX2/SDA2_46") (pintype "bidirectional"))
      (node (ref "U3") (pin "5") (pinfunction "1A2_5") (pintype "bidirectional"))
    )
    (net (code "58") (name "VDD") (class "Default")
      (node (ref "C5") (pin "2") (pinfunction "2_2") (pintype "passive"))
      (node (ref "C7") (pin "1") (pinfunction "1_1") (pintype "passive"))
      (node (ref "JP1") (pin "2") (pinfunction "2_2") (pintype "passive"))
      (node (ref "JP2") (pin "2") (pinfunction "2_2") (pintype "passive"))
      (node (ref "R1") (pin "2") (pinfunction "2_2") (pintype "passive"))
      (node (ref "R2") (pin "2") (pinfunction "2_2") (pintype "passive"))
      (node (ref "R6") (pin "2") (pinfunction "2_2") (pintype "passive"))
      (node (ref "U2") (pin "5") (pinfunction "OUT_5") (pintype "passive"))
      (node (ref "U3") (pin "1") (pinfunction "VCC_A_1") (pintype "bidirectional"))
      (node (ref "U3") (pin "2") (pinfunction "1DIR_2") (pintype "input"))
    )
    (net (code "59") (name "VDDOUT") (class "Default")
      (node (ref "MOD1") (pin "61") (pinfunction "VDDOUT_61") (pintype "bidirectional"))
      (node (ref "U2") (pin "3") (pinfunction "EN_3") (pintype "input"))
    )
    (net (code "60") (name "unconnected-(K1-Pad2)") (class "Default")
      (node (ref "K1") (pin "2") (pinfunction "2_2") (pintype "passive"))
    )
    (net (code "61") (name "unconnected-(MOD1C-RF0-Pad75)") (class "Default")
      (node (ref "MOD1") (pin "75") (pinfunction "RF0_75") (pintype "passive"))
    )
    (net (code "62") (name "unconnected-(MOD1D-CHARGE_CTRL-Pad22)") (class "Default")
      (node (ref "MOD1") (pin "22") (pinfunction "CHARGE_CTRL_22") (pintype "bidirectional"))
    )
    (net (code "63") (name "unconnected-(MOD1D-DC_CTRL-Pad21)") (class "Default")
      (node (ref "MOD1") (pin "21") (pinfunction "DC_CTRL_21") (pintype "bidirectional"))
    )
    (net (code "64") (name "unconnected-(MOD1D-VBATSW-Pad62)") (class "Default")
      (node (ref "MOD1") (pin "62") (pinfunction "VBATSW_62") (pintype "bidirectional"))
    )
    (net (code "65") (name "unconnected-(X4-Pad6)") (class "Default")
      (node (ref "X4") (pin "6") (pinfunction "6_6") (pintype "passive"))
    )
  )
)
